# nguon5v.net
KiCad netlist of a schematic drawn in Altium Designer
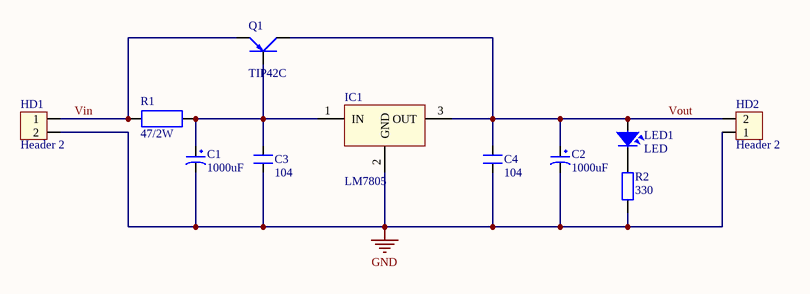
[diagram p0: nguon5v.SchDoc]

(export (version "E")
  (design (tool "Eeschema 10.0.6"))
  (components
    (comp (ref "C1")
      (value "1000uF")
      (footprint "CP1/2")
      (description "Cap P  0,1uF < 22uF , 16 - 50V")
      (libsource (lib "syhaunguyen") (part "CP1"))
    )
    (comp (ref "C2")
      (value "1000uF")
      (footprint "CP1/2")
      (description "Cap P  0,1uF < 22uF , 16 - 50V")
      (libsource (lib "syhaunguyen") (part "CP1"))
    )
    (comp (ref "C3")
      (value "104")
      (footprint "CN1.5")
      (description "Cap np 682pF => 104pF")
      (libsource (lib "syhaunguyen") (part "CN1.5"))
    )
    (comp (ref "C4")
      (value "104")
      (footprint "CN1.5")
      (description "Cap np 682pF => 104pF")
      (libsource (lib "syhaunguyen") (part "CN1.5"))
    )
    (comp (ref "HD1")
      (value "Header 2")
      (footprint "HED2")
      (description "Header 2 (Green)")
      (libsource (lib "syhaunguyen") (part "Hed2"))
    )
    (comp (ref "HD2")
      (value "Header 2")
      (footprint "HED2")
      (description "Header 2 (Green)")
      (libsource (lib "") (part "Hed2_1"))
    )
    (comp (ref "IC1")
      (value "LM7805")
      (footprint "QTO-220")
      (description "On ap +, from + 5 to + 24VDC")
      (libsource (lib "syhaunguyen") (part "LM78xx"))
    )
    (comp (ref "LED1")
      (value "LED")
      (footprint "LED-3")
      (description "LED Single colour Green and Red")
      (libsource (lib "syhaunguyen") (part "LED"))
    )
    (comp (ref "Q1")
      (value "TIP42C")
      (footprint "QTO-220")
      (description "PNP 2W, BCE")
      (libsource (lib "syhaunguyen") (part "TIP42C"))
    )
    (comp (ref "R1")
      (value "47/2W")
      (footprint "R2W")
      (description "Resistor 2W")
      (libsource (lib "syhaunguyen") (part "R2W"))
    )
    (comp (ref "R2")
      (value "330")
      (footprint "R1/4W")
      (description "Resistor 1/4W")
      (libsource (lib "syhaunguyen") (part "R1/4W"))
    )
  )
  (nets
    (net (code "1") (name "/Vin") (class "Default")
      (node (ref "HD1") (pin "1") (pinfunction "1_1") (pintype "passive"))
      (node (ref "Q1") (pin "3") (pinfunction "E_3") (pintype "passive"))
      (node (ref "R1") (pin "1") (pinfunction "1_1") (pintype "passive"))
    )
    (net (code "2") (name "/Vout") (class "Default")
      (node (ref "C2") (pin "1") (pinfunction "1_1") (pintype "passive"))
      (node (ref "C4") (pin "2") (pinfunction "2_2") (pintype "passive"))
      (node (ref "HD2") (pin "2") (pinfunction "2_2") (pintype "passive"))
      (node (ref "IC1") (pin "3") (pinfunction "OUT_3") (pintype "passive"))
      (node (ref "LED1") (pin "1") (pinfunction "1_1") (pintype "passive"))
      (node (ref "Q1") (pin "2") (pinfunction "C_2") (pintype "passive"))
    )
    (net (code "3") (name "GND") (class "Default")
      (node (ref "C1") (pin "2") (pinfunction "2_2") (pintype "passive"))
      (node (ref "C2") (pin "2") (pinfunction "2_2") (pintype "passive"))
      (node (ref "C3") (pin "1") (pinfunction "1_1") (pintype "passive"))
      (node (ref "C4") (pin "1") (pinfunction "1_1") (pintype "passive"))
      (node (ref "HD1") (pin "2") (pinfunction "2_2") (pintype "passive"))
      (node (ref "HD2") (pin "1") (pinfunction "1_1") (pintype "passive"))
      (node (ref "IC1") (pin "2") (pinfunction "GND_2") (pintype "passive"))
      (node (ref "R2") (pin "1") (pinfunction "1_1") (pintype "passive"))
    )
    (net (code "4") (name "Net-(IC1-IN)") (class "Default")
      (node (ref "C1") (pin "1") (pinfunction "1_1") (pintype "passive"))
      (node (ref "C3") (pin "2") (pinfunction "2_2") (pintype "passive"))
      (node (ref "IC1") (pin "1") (pinfunction "IN_1") (pintype "passive"))
      (node (ref "Q1") (pin "1") (pinfunction "B_1") (pintype "passive"))
      (node (ref "R1") (pin "2") (pinfunction "2_2") (pintype "passive"))
    )
    (net (code "5") (name "Net-(LED1-Pad2)") (class "Default")
      (node (ref "LED1") (pin "2") (pinfunction "2_2") (pintype "passive"))
      (node (ref "R2") (pin "2") (pinfunction "2_2") (pintype "passive"))
    )
  )
)
